# power.net
KiCad netlist of a schematic drawn in Altium Designer
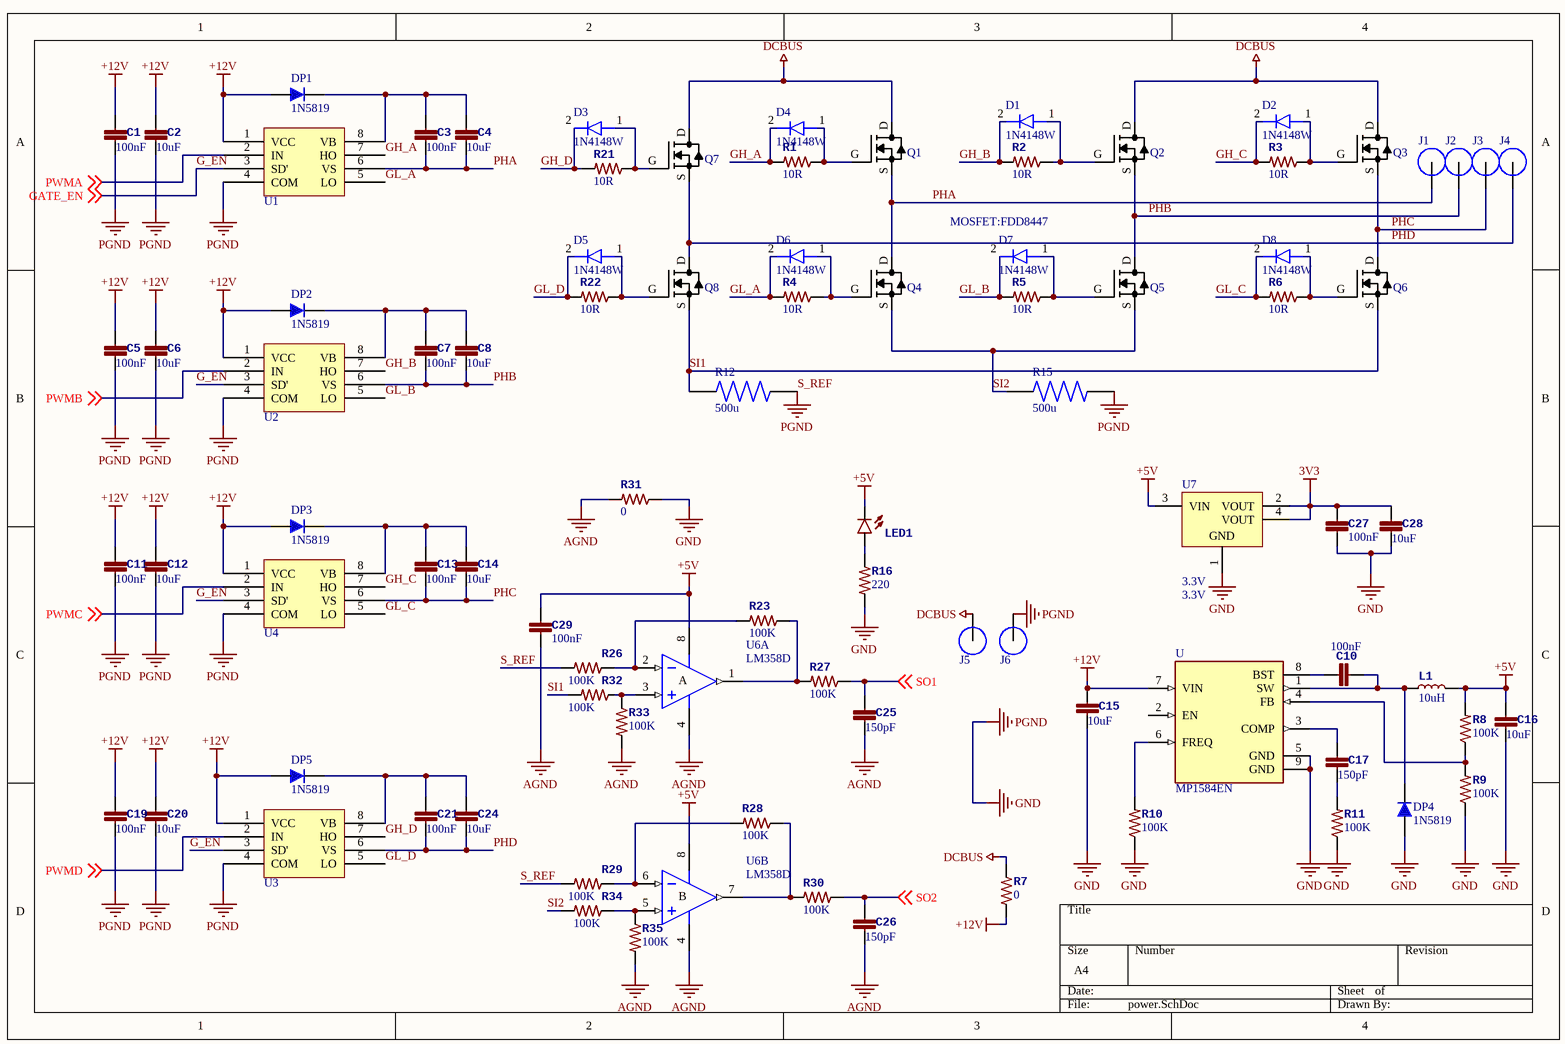
[diagram p0: power.SchDoc]

(export (version "E")
  (design (tool "Eeschema 10.0.6"))
  (components
    (comp (ref "C1")
      (value "100nF")
      (footprint "_1206")
      (fields (field (name "Comment") "Cap"))
      (libsource (lib "Passives_Integrated_Library") (part "Cap_1"))
    )
    (comp (ref "C2")
      (value "10uF")
      (footprint "_1206")
      (fields (field (name "Comment") "Cap"))
      (libsource (lib "Passives_Integrated_Library") (part "Cap_1"))
    )
    (comp (ref "C3")
      (value "100nF")
      (footprint "_1206")
      (fields (field (name "Comment") "Cap"))
      (libsource (lib "Passives_Integrated_Library") (part "Cap_1"))
    )
    (comp (ref "C4")
      (value "10uF")
      (footprint "_1206")
      (fields (field (name "Comment") "Cap"))
      (libsource (lib "Passives_Integrated_Library") (part "Cap_1"))
    )
    (comp (ref "C5")
      (value "100nF")
      (footprint "_1206")
      (fields (field (name "Comment") "Cap"))
      (libsource (lib "Passives_Integrated_Library") (part "Cap_1"))
    )
    (comp (ref "C6")
      (value "10uF")
      (footprint "_1206")
      (fields (field (name "Comment") "Cap"))
      (libsource (lib "Passives_Integrated_Library") (part "Cap_1"))
    )
    (comp (ref "C7")
      (value "100nF")
      (footprint "_1206")
      (fields (field (name "Comment") "Cap"))
      (libsource (lib "Passives_Integrated_Library") (part "Cap_1"))
    )
    (comp (ref "C8")
      (value "10uF")
      (footprint "_1206")
      (fields (field (name "Comment") "Cap"))
      (libsource (lib "Passives_Integrated_Library") (part "Cap_1"))
    )
    (comp (ref "C10")
      (value "100nF")
      (footprint "_0805")
      (fields (field (name "Comment") "Cap"))
      (libsource (lib "") (part "Cap_1_1"))
    )
    (comp (ref "C11")
      (value "100nF")
      (footprint "_1206")
      (fields (field (name "Comment") "Cap"))
      (libsource (lib "Passives_Integrated_Library") (part "Cap_1"))
    )
    (comp (ref "C12")
      (value "10uF")
      (footprint "_1206")
      (fields (field (name "Comment") "Cap"))
      (libsource (lib "Passives_Integrated_Library") (part "Cap_1"))
    )
    (comp (ref "C13")
      (value "100nF")
      (footprint "_1206")
      (fields (field (name "Comment") "Cap"))
      (libsource (lib "Passives_Integrated_Library") (part "Cap_1"))
    )
    (comp (ref "C14")
      (value "10uF")
      (footprint "_1206")
      (fields (field (name "Comment") "Cap"))
      (libsource (lib "Passives_Integrated_Library") (part "Cap_1"))
    )
    (comp (ref "C15")
      (value "10uF")
      (footprint "_1206")
      (fields (field (name "Comment") "Cap"))
      (libsource (lib "Passives_Integrated_Library") (part "Cap_1"))
    )
    (comp (ref "C16")
      (value "10uF")
      (footprint "_1206")
      (fields (field (name "Comment") "Cap"))
      (libsource (lib "Passives_Integrated_Library") (part "Cap_1"))
    )
    (comp (ref "C17")
      (value "150pF")
      (footprint "_0805")
      (fields (field (name "Comment") "Cap"))
      (libsource (lib "Passives_Integrated_Library") (part "Cap_1"))
    )
    (comp (ref "C19")
      (value "100nF")
      (footprint "_1206")
      (fields (field (name "Comment") "Cap"))
      (libsource (lib "Passives_Integrated_Library") (part "Cap_1"))
    )
    (comp (ref "C20")
      (value "10uF")
      (footprint "_1206")
      (fields (field (name "Comment") "Cap"))
      (libsource (lib "Passives_Integrated_Library") (part "Cap_1"))
    )
    (comp (ref "C21")
      (value "100nF")
      (footprint "_1206")
      (fields (field (name "Comment") "Cap"))
      (libsource (lib "Passives_Integrated_Library") (part "Cap_1"))
    )
    (comp (ref "C24")
      (value "10uF")
      (footprint "_1206")
      (fields (field (name "Comment") "Cap"))
      (libsource (lib "Passives_Integrated_Library") (part "Cap_1"))
    )
    (comp (ref "C25")
      (value "150pF")
      (footprint "_0805")
      (fields (field (name "Comment") "Cap"))
      (libsource (lib "Passives_Integrated_Library") (part "Cap_1"))
    )
    (comp (ref "C26")
      (value "150pF")
      (footprint "_0805")
      (fields (field (name "Comment") "Cap"))
      (libsource (lib "Passives_Integrated_Library") (part "Cap_1"))
    )
    (comp (ref "C27")
      (value "100nF")
      (footprint "_0805")
      (fields (field (name "Comment") "Cap"))
      (libsource (lib "") (part "Cap_1_2"))
    )
    (comp (ref "C28")
      (value "10uF")
      (footprint "_1206")
      (fields (field (name "Comment") "Cap"))
      (libsource (lib "Passives_Integrated_Library") (part "Cap_1"))
    )
    (comp (ref "C29")
      (value "100nF")
      (footprint "_0805")
      (fields (field (name "Comment") "Cap"))
      (libsource (lib "") (part "Cap_1_2"))
    )
    (comp (ref "D1")
      (value "1N4148W")
      (footprint "SOD523F")
      (fields (field (name "MF") "Micro Commercial"))
      (libsource (lib "1N4148W") (part "1N4148W"))
    )
    (comp (ref "D2")
      (value "1N4148W")
      (footprint "SOD523F")
      (fields (field (name "MF") "Micro Commercial"))
      (libsource (lib "1N4148W") (part "1N4148W"))
    )
    (comp (ref "D3")
      (value "1N4148W")
      (footprint "SOD523F")
      (fields (field (name "MF") "Micro Commercial"))
      (libsource (lib "1N4148W") (part "1N4148W"))
    )
    (comp (ref "D4")
      (value "1N4148W")
      (footprint "SOD523F")
      (fields (field (name "MF") "Micro Commercial"))
      (libsource (lib "1N4148W") (part "1N4148W"))
    )
    (comp (ref "D5")
      (value "1N4148W")
      (footprint "SOD523F")
      (fields (field (name "MF") "Micro Commercial"))
      (libsource (lib "1N4148W") (part "1N4148W"))
    )
    (comp (ref "D6")
      (value "1N4148W")
      (footprint "SOD523F")
      (fields (field (name "MF") "Micro Commercial"))
      (libsource (lib "1N4148W") (part "1N4148W"))
    )
    (comp (ref "D7")
      (value "1N4148W")
      (footprint "SOD523F")
      (fields (field (name "MF") "Micro Commercial"))
      (libsource (lib "1N4148W") (part "1N4148W"))
    )
    (comp (ref "D8")
      (value "1N4148W")
      (footprint "SOD523F")
      (fields (field (name "MF") "Micro Commercial"))
      (libsource (lib "1N4148W") (part "1N4148W"))
    )
    (comp (ref "DP1")
      (value "1N5819")
      (footprint "430X270D")
      (description "Schottkey Rectifiers")
      (fields (field (name "DESIGNER") "Abbas Basereh"))
      (libsource (lib "Diodes_Integrated_Library") (part "1N5819"))
    )
    (comp (ref "DP2")
      (value "1N5819")
      (footprint "430X270D")
      (description "Schottkey Rectifiers")
      (fields (field (name "DESIGNER") "Abbas Basereh"))
      (libsource (lib "Diodes_Integrated_Library") (part "1N5819"))
    )
    (comp (ref "DP3")
      (value "1N5819")
      (footprint "430X270D")
      (description "Schottkey Rectifiers")
      (fields (field (name "DESIGNER") "Abbas Basereh"))
      (libsource (lib "Diodes_Integrated_Library") (part "1N5819"))
    )
    (comp (ref "DP4")
      (value "1N5819")
      (footprint "430X270D")
      (description "Schottkey Rectifiers")
      (fields (field (name "DESIGNER") "Abbas Basereh"))
      (libsource (lib "Diodes_Integrated_Library") (part "1N5819"))
    )
    (comp (ref "DP5")
      (value "1N5819")
      (footprint "430X270D")
      (description "Schottkey Rectifiers")
      (fields (field (name "DESIGNER") "Abbas Basereh"))
      (libsource (lib "Diodes_Integrated_Library") (part "1N5819"))
    )
    (comp (ref "J1")
      (value "~")
      (footprint "M3 Spade Hole")
      (description "M3 Spade Terminal")
      (libsource (lib "CustomComponents") (part "M3 Spade Terminal"))
    )
    (comp (ref "J2")
      (value "~")
      (footprint "M3 Spade Hole")
      (description "M3 Spade Terminal")
      (libsource (lib "CustomComponents") (part "M3 Spade Terminal"))
    )
    (comp (ref "J3")
      (value "~")
      (footprint "M3 Spade Hole")
      (description "M3 Spade Terminal")
      (libsource (lib "CustomComponents") (part "M3 Spade Terminal"))
    )
    (comp (ref "J4")
      (value "~")
      (footprint "M3 Spade Hole")
      (description "M3 Spade Terminal")
      (libsource (lib "ali_drv_parts") (part "M3 Spade Terminal"))
    )
    (comp (ref "J5")
      (value "~")
      (footprint "M3 Spade Hole")
      (description "M3 Spade Terminal")
      (libsource (lib "CustomComponents") (part "M3 Spade Terminal"))
    )
    (comp (ref "J6")
      (value "~")
      (footprint "M3 Spade Hole")
      (description "M3 Spade Terminal")
      (libsource (lib "CustomComponents") (part "M3 Spade Terminal"))
    )
    (comp (ref "L1")
      (value "10uH")
      (footprint "_INDUCTOR-SMD-6.0mm")
      (fields (field (name "Comment") "Inductor"))
      (libsource (lib "Passives_Integrated_Library") (part "Inductor"))
    )
    (comp (ref "LED1")
      (value "LED")
      (footprint "_LED-0805")
      (libsource (lib "Diodes_Integrated_Library") (part "LED"))
    )
    (comp (ref "Q1")
      (value "FILL_FOOTPRINT")
      (footprint "TO229P994X240-3N")
      (description "MOSFET N-CH 30V 13A SO8FL")
      (fields
        (field (name "MANUFACTURER") "ON Semiconductor")
        (field (name "MANUFACTURER PART NUMBER") "NTMFS4935NT1G")
      )
      (libsource (lib "Integrated_Library1") (part "NTMFS4935NT1G"))
    )
    (comp (ref "Q2")
      (value "FILL_FOOTPRINT")
      (footprint "TO229P994X240-3N")
      (description "MOSFET N-CH 30V 13A SO8FL")
      (fields
        (field (name "MANUFACTURER") "ON Semiconductor")
        (field (name "MANUFACTURER PART NUMBER") "NTMFS4935NT1G")
      )
      (libsource (lib "Integrated_Library1") (part "NTMFS4935NT1G"))
    )
    (comp (ref "Q3")
      (value "FILL_FOOTPRINT")
      (footprint "TO229P994X240-3N")
      (description "MOSFET N-CH 30V 13A SO8FL")
      (fields
        (field (name "MANUFACTURER") "ON Semiconductor")
        (field (name "MANUFACTURER PART NUMBER") "NTMFS4935NT1G")
      )
      (libsource (lib "Integrated_Library1") (part "NTMFS4935NT1G"))
    )
    (comp (ref "Q4")
      (value "FILL_FOOTPRINT")
      (footprint "TO229P994X240-3N")
      (description "MOSFET N-CH 30V 13A SO8FL")
      (fields
        (field (name "MANUFACTURER") "ON Semiconductor")
        (field (name "MANUFACTURER PART NUMBER") "NTMFS4935NT1G")
      )
      (libsource (lib "Integrated_Library1") (part "NTMFS4935NT1G"))
    )
    (comp (ref "Q5")
      (value "FILL_FOOTPRINT")
      (footprint "TO229P994X240-3N")
      (description "MOSFET N-CH 30V 13A SO8FL")
      (fields
        (field (name "MANUFACTURER") "ON Semiconductor")
        (field (name "MANUFACTURER PART NUMBER") "NTMFS4935NT1G")
      )
      (libsource (lib "Integrated_Library1") (part "NTMFS4935NT1G"))
    )
    (comp (ref "Q6")
      (value "FILL_FOOTPRINT")
      (footprint "TO229P994X240-3N")
      (description "MOSFET N-CH 30V 13A SO8FL")
      (fields
        (field (name "MANUFACTURER") "ON Semiconductor")
        (field (name "MANUFACTURER PART NUMBER") "NTMFS4935NT1G")
      )
      (libsource (lib "Integrated_Library1") (part "NTMFS4935NT1G"))
    )
    (comp (ref "Q7")
      (value "FILL_FOOTPRINT")
      (footprint "TO229P994X240-3N")
      (description "MOSFET N-CH 30V 13A SO8FL")
      (fields
        (field (name "MANUFACTURER") "ON Semiconductor")
        (field (name "MANUFACTURER PART NUMBER") "NTMFS4935NT1G")
      )
      (libsource (lib "ali_drv_parts") (part "NTMFS4935NT1G"))
    )
    (comp (ref "Q8")
      (value "FILL_FOOTPRINT")
      (footprint "TO229P994X240-3N")
      (description "MOSFET N-CH 30V 13A SO8FL")
      (fields
        (field (name "MANUFACTURER") "ON Semiconductor")
        (field (name "MANUFACTURER PART NUMBER") "NTMFS4935NT1G")
      )
      (libsource (lib "ali_drv_parts") (part "NTMFS4935NT1G"))
    )
    (comp (ref "R1")
      (value "10R")
      (footprint "_0805")
      (fields (field (name "Comment") "Resistor"))
      (libsource (lib "Passives_Integrated_Library") (part "Resistor"))
    )
    (comp (ref "R2")
      (value "10R")
      (footprint "_0805")
      (fields (field (name "Comment") "Resistor"))
      (libsource (lib "Passives_Integrated_Library") (part "Resistor"))
    )
    (comp (ref "R3")
      (value "10R")
      (footprint "_0805")
      (fields (field (name "Comment") "Resistor"))
      (libsource (lib "Passives_Integrated_Library") (part "Resistor"))
    )
    (comp (ref "R4")
      (value "10R")
      (footprint "_0805")
      (fields (field (name "Comment") "Resistor"))
      (libsource (lib "Passives_Integrated_Library") (part "Resistor"))
    )
    (comp (ref "R5")
      (value "10R")
      (footprint "_0805")
      (fields (field (name "Comment") "Resistor"))
      (libsource (lib "Passives_Integrated_Library") (part "Resistor"))
    )
    (comp (ref "R6")
      (value "10R")
      (footprint "_0805")
      (fields (field (name "Comment") "Resistor"))
      (libsource (lib "Passives_Integrated_Library") (part "Resistor"))
    )
    (comp (ref "R7")
      (value "0")
      (footprint "_1206")
      (fields (field (name "Comment") "Resistor"))
      (libsource (lib "Passives_Integrated_Library") (part "Resistor"))
    )
    (comp (ref "R8")
      (value "100K")
      (footprint "_0805")
      (fields (field (name "Comment") "Resistor"))
      (libsource (lib "Passives_Integrated_Library") (part "Resistor"))
    )
    (comp (ref "R9")
      (value "100K")
      (footprint "_0805")
      (fields (field (name "Comment") "Resistor"))
      (libsource (lib "Passives_Integrated_Library") (part "Resistor"))
    )
    (comp (ref "R10")
      (value "100K")
      (footprint "_0805")
      (fields (field (name "Comment") "Resistor"))
      (libsource (lib "Passives_Integrated_Library") (part "Resistor"))
    )
    (comp (ref "R11")
      (value "100K")
      (footprint "_0805")
      (fields (field (name "Comment") "Resistor"))
      (libsource (lib "Passives_Integrated_Library") (part "Resistor"))
    )
    (comp (ref "R12")
      (value "500u")
      (footprint "RESC6332X64N")
      (fields (field (name "MP") "Y162820K0000D0W"))
      (libsource (lib "ali_drv_parts") (part "Y162820K0000D0W"))
    )
    (comp (ref "R15")
      (value "500u")
      (footprint "RESC6332X64N")
      (fields (field (name "MP") "Y162820K0000D0W"))
      (libsource (lib "ali_drv_parts") (part "Y162820K0000D0W"))
    )
    (comp (ref "R16")
      (value "220")
      (footprint "_0805")
      (fields (field (name "Comment") "Resistor"))
      (libsource (lib "Passives_Integrated_Library") (part "Resistor"))
    )
    (comp (ref "R21")
      (value "10R")
      (footprint "_0805")
      (fields (field (name "Comment") "Resistor"))
      (libsource (lib "Passives_Integrated_Library") (part "Resistor"))
    )
    (comp (ref "R22")
      (value "10R")
      (footprint "_0805")
      (fields (field (name "Comment") "Resistor"))
      (libsource (lib "Passives_Integrated_Library") (part "Resistor"))
    )
    (comp (ref "R23")
      (value "100K")
      (footprint "_0805")
      (fields (field (name "Comment") "Resistor"))
      (libsource (lib "Passives_Integrated_Library") (part "Resistor"))
    )
    (comp (ref "R26")
      (value "100K")
      (footprint "_0805")
      (fields (field (name "Comment") "Resistor"))
      (libsource (lib "Passives_Integrated_Library") (part "Resistor"))
    )
    (comp (ref "R27")
      (value "100K")
      (footprint "_0805")
      (fields (field (name "Comment") "Resistor"))
      (libsource (lib "Passives_Integrated_Library") (part "Resistor"))
    )
    (comp (ref "R28")
      (value "100K")
      (footprint "_0805")
      (fields (field (name "Comment") "Resistor"))
      (libsource (lib "Passives_Integrated_Library") (part "Resistor"))
    )
    (comp (ref "R29")
      (value "100K")
      (footprint "_0805")
      (fields (field (name "Comment") "Resistor"))
      (libsource (lib "Passives_Integrated_Library") (part "Resistor"))
    )
    (comp (ref "R30")
      (value "100K")
      (footprint "_0805")
      (fields (field (name "Comment") "Resistor"))
      (libsource (lib "Passives_Integrated_Library") (part "Resistor"))
    )
    (comp (ref "R31")
      (value "0")
      (footprint "_0805")
      (fields (field (name "Comment") "Resistor"))
      (libsource (lib "Passives_Integrated_Library") (part "Resistor"))
    )
    (comp (ref "R32")
      (value "100K")
      (footprint "_0805")
      (fields (field (name "Comment") "Resistor"))
      (libsource (lib "Passives_Integrated_Library") (part "Resistor"))
    )
    (comp (ref "R33")
      (value "100K")
      (footprint "_0805")
      (fields (field (name "Comment") "Resistor"))
      (libsource (lib "Passives_Integrated_Library") (part "Resistor"))
    )
    (comp (ref "R34")
      (value "100K")
      (footprint "_0805")
      (fields (field (name "Comment") "Resistor"))
      (libsource (lib "Passives_Integrated_Library") (part "Resistor"))
    )
    (comp (ref "R35")
      (value "100K")
      (footprint "_0805")
      (fields (field (name "Comment") "Resistor"))
      (libsource (lib "Passives_Integrated_Library") (part "Resistor"))
    )
    (comp (ref "U")
      (value "MP1584EN")
      (footprint "SOIC127P600X170-9N")
      (fields (field (name "MF") "Monolithic Power"))
      (libsource (lib "MP1584EN") (part "MP1584EN"))
    )
    (comp (ref "U1")
      (value "IR2104")
      (footprint "_SO08")
      (libsource (lib "Power_Electronics_Integrated_Library") (part "IR2104"))
    )
    (comp (ref "U2")
      (value "IR2104")
      (footprint "_SO08")
      (libsource (lib "Power_Electronics_Integrated_Library") (part "IR2104"))
    )
    (comp (ref "U3")
      (value "IR2104")
      (footprint "_SO08")
      (libsource (lib "Power_Electronics_Integrated_Library") (part "IR2104"))
    )
    (comp (ref "U4")
      (value "IR2104")
      (footprint "_SO08")
      (libsource (lib "Power_Electronics_Integrated_Library") (part "IR2104"))
    )
    (comp (ref "U6")
      (value "LM358D")
      (footprint "D008_L")
      (description "Dual Operational Amplifier")
      (fields (field (name "PUBLISHER") "Altium Limited"))
      (libsource (lib "TI Operational Amplifier") (part "LM358D"))
    )
    (comp (ref "U7")
      (value "3.3V")
      (footprint "_SOT223")
      (fields (field (name "ALTIUM_VALUE") "3.3V"))
      (libsource (lib "Regulators_Integrated_Library") (part "LD1117"))
    )
  )
  (nets
    (net (code "1") (name "+5V") (class "Default")
      (node (ref "C16") (pin "1") (pinfunction "1_1") (pintype "passive"))
      (node (ref "C29") (pin "2") (pinfunction "2_2") (pintype "passive"))
      (node (ref "L1") (pin "2") (pinfunction "2_2") (pintype "passive"))
      (node (ref "LED1") (pin "K") (pinfunction "K_K") (pintype "passive"))
      (node (ref "R8") (pin "2") (pinfunction "2_2") (pintype "passive"))
      (node (ref "U6") (pin "8") (pinfunction "V+_8") (pintype "power_in"))
      (node (ref "U7") (pin "3") (pinfunction "VIN_3") (pintype "power_in"))
    )
    (net (code "2") (name "+12V") (class "Default")
      (node (ref "C1") (pin "1") (pinfunction "1_1") (pintype "passive"))
      (node (ref "C11") (pin "1") (pinfunction "1_1") (pintype "passive"))
      (node (ref "C12") (pin "1") (pinfunction "1_1") (pintype "passive"))
      (node (ref "C15") (pin "1") (pinfunction "1_1") (pintype "passive"))
      (node (ref "C19") (pin "1") (pinfunction "1_1") (pintype "passive"))
      (node (ref "C2") (pin "1") (pinfunction "1_1") (pintype "passive"))
      (node (ref "C20") (pin "1") (pinfunction "1_1") (pintype "passive"))
      (node (ref "C5") (pin "1") (pinfunction "1_1") (pintype "passive"))
      (node (ref "C6") (pin "1") (pinfunction "1_1") (pintype "passive"))
      (node (ref "DP1") (pin "1") (pintype "passive"))
      (node (ref "DP2") (pin "1") (pintype "passive"))
      (node (ref "DP3") (pin "1") (pintype "passive"))
      (node (ref "DP5") (pin "1") (pintype "passive"))
      (node (ref "R7") (pin "2") (pinfunction "2_2") (pintype "passive"))
      (node (ref "U") (pin "7") (pinfunction "VIN_7") (pintype "input"))
      (node (ref "U1") (pin "1") (pinfunction "VCC_1") (pintype "passive"))
      (node (ref "U2") (pin "1") (pinfunction "VCC_1") (pintype "passive"))
      (node (ref "U3") (pin "1") (pinfunction "VCC_1") (pintype "passive"))
      (node (ref "U4") (pin "1") (pinfunction "VCC_1") (pintype "passive"))
    )
    (net (code "3") (name "/GH_A") (class "Default")
      (node (ref "D4") (pin "2") (pinfunction "C1_2") (pintype "passive"))
      (node (ref "R1") (pin "2") (pinfunction "2_2") (pintype "passive"))
      (node (ref "U1") (pin "7") (pinfunction "HO_7") (pintype "passive"))
    )
    (net (code "4") (name "/GH_B") (class "Default")
      (node (ref "D1") (pin "2") (pinfunction "C1_2") (pintype "passive"))
      (node (ref "R2") (pin "2") (pinfunction "2_2") (pintype "passive"))
      (node (ref "U2") (pin "7") (pinfunction "HO_7") (pintype "passive"))
    )
    (net (code "5") (name "/GH_C") (class "Default")
      (node (ref "D2") (pin "2") (pinfunction "C1_2") (pintype "passive"))
      (node (ref "R3") (pin "2") (pinfunction "2_2") (pintype "passive"))
      (node (ref "U4") (pin "7") (pinfunction "HO_7") (pintype "passive"))
    )
    (net (code "6") (name "/GH_D") (class "Default")
      (node (ref "D3") (pin "2") (pinfunction "C1_2") (pintype "passive"))
      (node (ref "R21") (pin "2") (pinfunction "2_2") (pintype "passive"))
      (node (ref "U3") (pin "7") (pinfunction "HO_7") (pintype "passive"))
    )
    (net (code "7") (name "/GL_A") (class "Default")
      (node (ref "D6") (pin "2") (pinfunction "C1_2") (pintype "passive"))
      (node (ref "R4") (pin "2") (pinfunction "2_2") (pintype "passive"))
      (node (ref "U1") (pin "5") (pinfunction "LO_5") (pintype "passive"))
    )
    (net (code "8") (name "/GL_B") (class "Default")
      (node (ref "D7") (pin "2") (pinfunction "C1_2") (pintype "passive"))
      (node (ref "R5") (pin "2") (pinfunction "2_2") (pintype "passive"))
      (node (ref "U2") (pin "5") (pinfunction "LO_5") (pintype "passive"))
    )
    (net (code "9") (name "/GL_C") (class "Default")
      (node (ref "D8") (pin "2") (pinfunction "C1_2") (pintype "passive"))
      (node (ref "R6") (pin "2") (pinfunction "2_2") (pintype "passive"))
      (node (ref "U4") (pin "5") (pinfunction "LO_5") (pintype "passive"))
    )
    (net (code "10") (name "/GL_D") (class "Default")
      (node (ref "D5") (pin "2") (pinfunction "C1_2") (pintype "passive"))
      (node (ref "R22") (pin "2") (pinfunction "2_2") (pintype "passive"))
      (node (ref "U3") (pin "5") (pinfunction "LO_5") (pintype "passive"))
    )
    (net (code "11") (name "/PHA") (class "Default")
      (node (ref "C3") (pin "2") (pinfunction "2_2") (pintype "passive"))
      (node (ref "C4") (pin "2") (pinfunction "2_2") (pintype "passive"))
      (node (ref "J1") (pin "1") (pinfunction "1_1") (pintype "passive"))
      (node (ref "Q1") (pin "S") (pinfunction "S_S") (pintype "passive"))
      (node (ref "Q4") (pin "D") (pinfunction "D_D") (pintype "passive"))
      (node (ref "U1") (pin "6") (pinfunction "VS_6") (pintype "passive"))
    )
    (net (code "12") (name "/PHB") (class "Default")
      (node (ref "C7") (pin "2") (pinfunction "2_2") (pintype "passive"))
      (node (ref "C8") (pin "2") (pinfunction "2_2") (pintype "passive"))
      (node (ref "J2") (pin "1") (pinfunction "1_1") (pintype "passive"))
      (node (ref "Q2") (pin "S") (pinfunction "S_S") (pintype "passive"))
      (node (ref "Q5") (pin "D") (pinfunction "D_D") (pintype "passive"))
      (node (ref "U2") (pin "6") (pinfunction "VS_6") (pintype "passive"))
    )
    (net (code "13") (name "/PHC") (class "Default")
      (node (ref "C13") (pin "2") (pinfunction "2_2") (pintype "passive"))
      (node (ref "C14") (pin "2") (pinfunction "2_2") (pintype "passive"))
      (node (ref "J3") (pin "1") (pinfunction "1_1") (pintype "passive"))
      (node (ref "Q3") (pin "S") (pinfunction "S_S") (pintype "passive"))
      (node (ref "Q6") (pin "D") (pinfunction "D_D") (pintype "passive"))
      (node (ref "U4") (pin "6") (pinfunction "VS_6") (pintype "passive"))
    )
    (net (code "14") (name "/PHD") (class "Default")
      (node (ref "C21") (pin "2") (pinfunction "2_2") (pintype "passive"))
      (node (ref "C24") (pin "2") (pinfunction "2_2") (pintype "passive"))
      (node (ref "J4") (pin "1") (pinfunction "1_1") (pintype "passive"))
      (node (ref "Q7") (pin "S") (pinfunction "S_S") (pintype "passive"))
      (node (ref "Q8") (pin "D") (pinfunction "D_D") (pintype "passive"))
      (node (ref "U3") (pin "6") (pinfunction "VS_6") (pintype "passive"))
    )
    (net (code "15") (name "/SI1") (class "Default")
      (node (ref "Q6") (pin "S") (pinfunction "S_S") (pintype "passive"))
      (node (ref "Q8") (pin "S") (pinfunction "S_S") (pintype "passive"))
      (node (ref "R12") (pin "2") (pinfunction "2_2") (pintype "passive"))
      (node (ref "R32") (pin "2") (pinfunction "2_2") (pintype "passive"))
    )
    (net (code "16") (name "/SI2") (class "Default")
      (node (ref "Q4") (pin "S") (pinfunction "S_S") (pintype "passive"))
      (node (ref "Q5") (pin "S") (pinfunction "S_S") (pintype "passive"))
      (node (ref "R15") (pin "2") (pinfunction "2_2") (pintype "passive"))
      (node (ref "R34") (pin "2") (pinfunction "2_2") (pintype "passive"))
    )
    (net (code "17") (name "3V3") (class "Default")
      (node (ref "C27") (pin "2") (pinfunction "2_2") (pintype "passive"))
      (node (ref "C28") (pin "1") (pinfunction "1_1") (pintype "passive"))
      (node (ref "U7") (pin "2") (pinfunction "VOUT_2") (pintype "power_in"))
      (node (ref "U7") (pin "4") (pinfunction "VOUT_4") (pintype "power_in"))
    )
    (net (code "18") (name "AGND") (class "Default")
      (node (ref "C25") (pin "2") (pinfunction "2_2") (pintype "passive"))
      (node (ref "C26") (pin "2") (pinfunction "2_2") (pintype "passive"))
      (node (ref "C29") (pin "1") (pinfunction "1_1") (pintype "passive"))
      (node (ref "R31") (pin "2") (pinfunction "2_2") (pintype "passive"))
      (node (ref "R33") (pin "2") (pinfunction "2_2") (pintype "passive"))
      (node (ref "R35") (pin "2") (pinfunction "2_2") (pintype "passive"))
      (node (ref "U6") (pin "4") (pinfunction "V-_4") (pintype "power_in"))
    )
    (net (code "19") (name "DCBUS") (class "Default")
      (node (ref "J5") (pin "1") (pinfunction "1_1") (pintype "passive"))
      (node (ref "Q1") (pin "D") (pinfunction "D_D") (pintype "passive"))
      (node (ref "Q2") (pin "D") (pinfunction "D_D") (pintype "passive"))
      (node (ref "Q3") (pin "D") (pinfunction "D_D") (pintype "passive"))
      (node (ref "Q7") (pin "D") (pinfunction "D_D") (pintype "passive"))
      (node (ref "R7") (pin "1") (pinfunction "1_1") (pintype "passive"))
    )
    (net (code "20") (name "GATE_EN") (class "Default")
      (node (ref "U1") (pin "3") (pinfunction "SD'_3") (pintype "passive"))
      (node (ref "U2") (pin "3") (pinfunction "SD'_3") (pintype "passive"))
      (node (ref "U3") (pin "3") (pinfunction "SD'_3") (pintype "passive"))
      (node (ref "U4") (pin "3") (pinfunction "SD'_3") (pintype "passive"))
    )
    (net (code "21") (name "GND") (class "Default")
      (node (ref "C1") (pin "2") (pinfunction "2_2") (pintype "passive"))
      (node (ref "C11") (pin "2") (pinfunction "2_2") (pintype "passive"))
      (node (ref "C12") (pin "2") (pinfunction "2_2") (pintype "passive"))
      (node (ref "C15") (pin "2") (pinfunction "2_2") (pintype "passive"))
      (node (ref "C16") (pin "2") (pinfunction "2_2") (pintype "passive"))
      (node (ref "C19") (pin "2") (pinfunction "2_2") (pintype "passive"))
      (node (ref "C2") (pin "2") (pinfunction "2_2") (pintype "passive"))
      (node (ref "C20") (pin "2") (pinfunction "2_2") (pintype "passive"))
      (node (ref "C27") (pin "1") (pinfunction "1_1") (pintype "passive"))
      (node (ref "C28") (pin "2") (pinfunction "2_2") (pintype "passive"))
      (node (ref "C5") (pin "2") (pinfunction "2_2") (pintype "passive"))
      (node (ref "C6") (pin "2") (pinfunction "2_2") (pintype "passive"))
      (node (ref "DP4") (pin "1") (pintype "passive"))
      (node (ref "J6") (pin "1") (pinfunction "1_1") (pintype "passive"))
      (node (ref "R10") (pin "1") (pinfunction "1_1") (pintype "passive"))
      (node (ref "R11") (pin "1") (pinfunction "1_1") (pintype "passive"))
      (node (ref "R12") (pin "1") (pinfunction "1_1") (pintype "passive"))
      (node (ref "R15") (pin "1") (pinfunction "1_1") (pintype "passive"))
      (node (ref "R16") (pin "2") (pinfunction "2_2") (pintype "passive"))
      (node (ref "R26") (pin "2") (pinfunction "2_2") (pintype "passive"))
      (node (ref "R29") (pin "2") (pinfunction "2_2") (pintype "passive"))
      (node (ref "R31") (pin "1") (pinfunction "1_1") (pintype "passive"))
      (node (ref "R9") (pin "1") (pinfunction "1_1") (pintype "passive"))
      (node (ref "U") (pin "5") (pinfunction "GND_5") (pintype "power_in"))
      (node (ref "U") (pin "9") (pinfunction "GND_9") (pintype "power_in"))
      (node (ref "U1") (pin "4") (pinfunction "COM_4") (pintype "passive"))
      (node (ref "U2") (pin "4") (pinfunction "COM_4") (pintype "passive"))
      (node (ref "U3") (pin "4") (pinfunction "COM_4") (pintype "passive"))
      (node (ref "U4") (pin "4") (pinfunction "COM_4") (pintype "passive"))
      (node (ref "U7") (pin "1") (pinfunction "GND_1") (pintype "power_in"))
    )
    (net (code "22") (name "Net-(C17-Pad2)") (class "Default")
      (node (ref "C17") (pin "2") (pinfunction "2_2") (pintype "passive"))
      (node (ref "R11") (pin "2") (pinfunction "2_2") (pintype "passive"))
    )
    (net (code "23") (name "Net-(D1-A1)") (class "Default")
      (node (ref "D1") (pin "1") (pinfunction "A1_1") (pintype "passive"))
      (node (ref "Q2") (pin "G") (pinfunction "G_G") (pintype "passive"))
      (node (ref "R2") (pin "1") (pinfunction "1_1") (pintype "passive"))
    )
    (net (code "24") (name "Net-(D2-A1)") (class "Default")
      (node (ref "D2") (pin "1") (pinfunction "A1_1") (pintype "passive"))
      (node (ref "Q3") (pin "G") (pinfunction "G_G") (pintype "passive"))
      (node (ref "R3") (pin "1") (pinfunction "1_1") (pintype "passive"))
    )
    (net (code "25") (name "Net-(D3-A1)") (class "Default")
      (node (ref "D3") (pin "1") (pinfunction "A1_1") (pintype "passive"))
      (node (ref "Q7") (pin "G") (pinfunction "G_G") (pintype "passive"))
      (node (ref "R21") (pin "1") (pinfunction "1_1") (pintype "passive"))
    )
    (net (code "26") (name "Net-(D4-A1)") (class "Default")
      (node (ref "D4") (pin "1") (pinfunction "A1_1") (pintype "passive"))
      (node (ref "Q1") (pin "G") (pinfunction "G_G") (pintype "passive"))
      (node (ref "R1") (pin "1") (pinfunction "1_1") (pintype "passive"))
    )
    (net (code "27") (name "Net-(D5-A1)") (class "Default")
      (node (ref "D5") (pin "1") (pinfunction "A1_1") (pintype "passive"))
      (node (ref "Q8") (pin "G") (pinfunction "G_G") (pintype "passive"))
      (node (ref "R22") (pin "1") (pinfunction "1_1") (pintype "passive"))
    )
    (net (code "28") (name "Net-(D6-A1)") (class "Default")
      (node (ref "D6") (pin "1") (pinfunction "A1_1") (pintype "passive"))
      (node (ref "Q4") (pin "G") (pinfunction "G_G") (pintype "passive"))
      (node (ref "R4") (pin "1") (pinfunction "1_1") (pintype "passive"))
    )
    (net (code "29") (name "Net-(D7-A1)") (class "Default")
      (node (ref "D7") (pin "1") (pinfunction "A1_1") (pintype "passive"))
      (node (ref "Q5") (pin "G") (pinfunction "G_G") (pintype "passive"))
      (node (ref "R5") (pin "1") (pinfunction "1_1") (pintype "passive"))
    )
    (net (code "30") (name "Net-(D8-A1)") (class "Default")
      (node (ref "D8") (pin "1") (pinfunction "A1_1") (pintype "passive"))
      (node (ref "Q6") (pin "G") (pinfunction "G_G") (pintype "passive"))
      (node (ref "R6") (pin "1") (pinfunction "1_1") (pintype "passive"))
    )
    (net (code "31") (name "Net-(LED1-PadA)") (class "Default")
      (node (ref "LED1") (pin "A") (pinfunction "A_A") (pintype "passive"))
      (node (ref "R16") (pin "1") (pinfunction "1_1") (pintype "passive"))
    )
    (net (code "32") (name "Net-(U-BST)") (class "Default")
      (node (ref "C10") (pin "1") (pinfunction "1_1") (pintype "passive"))
      (node (ref "U") (pin "8") (pinfunction "BST_8") (pintype "passive"))
    )
    (net (code "33") (name "Net-(U-COMP)") (class "Default")
      (node (ref "C17") (pin "1") (pinfunction "1_1") (pintype "passive"))
      (node (ref "U") (pin "3") (pinfunction "COMP_3") (pintype "output"))
    )
    (net (code "34") (name "Net-(U-FB)") (class "Default")
      (node (ref "R8") (pin "1") (pinfunction "1_1") (pintype "passive"))
      (node (ref "R9") (pin "2") (pinfunction "2_2") (pintype "passive"))
      (node (ref "U") (pin "4") (pinfunction "FB_4") (pintype "input"))
    )
    (net (code "35") (name "Net-(U-FREQ)") (class "Default")
      (node (ref "R10") (pin "2") (pinfunction "2_2") (pintype "passive"))
      (node (ref "U") (pin "6") (pinfunction "FREQ_6") (pintype "input"))
    )
    (net (code "36") (name "Net-(U-SW)") (class "Default")
      (node (ref "C10") (pin "2") (pinfunction "2_2") (pintype "passive"))
      (node (ref "DP4") (pin "2") (pintype "passive"))
      (node (ref "L1") (pin "1") (pinfunction "1_1") (pintype "passive"))
      (node (ref "U") (pin "1") (pinfunction "SW_1") (pintype "output"))
    )
    (net (code "37") (name "Net-(U1-VB)") (class "Default")
      (node (ref "C3") (pin "1") (pinfunction "1_1") (pintype "passive"))
      (node (ref "C4") (pin "1") (pinfunction "1_1") (pintype "passive"))
      (node (ref "DP1") (pin "2") (pintype "passive"))
      (node (ref "U1") (pin "8") (pinfunction "VB_8") (pintype "passive"))
    )
    (net (code "38") (name "Net-(U2-VB)") (class "Default")
      (node (ref "C7") (pin "1") (pinfunction "1_1") (pintype "passive"))
      (node (ref "C8") (pin "1") (pinfunction "1_1") (pintype "passive"))
      (node (ref "DP2") (pin "2") (pintype "passive"))
      (node (ref "U2") (pin "8") (pinfunction "VB_8") (pintype "passive"))
    )
    (net (code "39") (name "Net-(U3-VB)") (class "Default")
      (node (ref "C21") (pin "1") (pinfunction "1_1") (pintype "passive"))
      (node (ref "C24") (pin "1") (pinfunction "1_1") (pintype "passive"))
      (node (ref "DP5") (pin "2") (pintype "passive"))
      (node (ref "U3") (pin "8") (pinfunction "VB_8") (pintype "passive"))
    )
    (net (code "40") (name "Net-(U4-VB)") (class "Default")
      (node (ref "C13") (pin "1") (pinfunction "1_1") (pintype "passive"))
      (node (ref "C14") (pin "1") (pinfunction "1_1") (pintype "passive"))
      (node (ref "DP3") (pin "2") (pintype "passive"))
      (node (ref "U4") (pin "8") (pinfunction "VB_8") (pintype "passive"))
    )
    (net (code "41") (name "Net-(U6A-IN+)") (class "Default")
      (node (ref "R32") (pin "1") (pinfunction "1_1") (pintype "passive"))
      (node (ref "R33") (pin "1") (pinfunction "1_1") (pintype "passive"))
      (node (ref "U6") (pin "3") (pinfunction "IN+_3") (pintype "input"))
    )
    (net (code "42") (name "Net-(U6A-IN-)") (class "Default")
      (node (ref "R23") (pin "2") (pinfunction "2_2") (pintype "passive"))
      (node (ref "R26") (pin "1") (pinfunction "1_1") (pintype "passive"))
      (node (ref "U6") (pin "2") (pinfunction "IN-_2") (pintype "input"))
    )
    (net (code "43") (name "Net-(U6A-OUT)") (class "Default")
      (node (ref "R23") (pin "1") (pinfunction "1_1") (pintype "passive"))
      (node (ref "R27") (pin "2") (pinfunction "2_2") (pintype "passive"))
      (node (ref "U6") (pin "1") (pinfunction "OUT_1") (pintype "output"))
    )
    (net (code "44") (name "Net-(U6B-IN+)") (class "Default")
      (node (ref "R34") (pin "1") (pinfunction "1_1") (pintype "passive"))
      (node (ref "R35") (pin "1") (pinfunction "1_1") (pintype "passive"))
      (node (ref "U6") (pin "5") (pinfunction "IN+_5") (pintype "input"))
    )
    (net (code "45") (name "Net-(U6B-IN-)") (class "Default")
      (node (ref "R28") (pin "2") (pinfunction "2_2") (pintype "passive"))
      (node (ref "R29") (pin "1") (pinfunction "1_1") (pintype "passive"))
      (node (ref "U6") (pin "6") (pinfunction "IN-_6") (pintype "input"))
    )
    (net (code "46") (name "Net-(U6B-OUT)") (class "Default")
      (node (ref "R28") (pin "1") (pinfunction "1_1") (pintype "passive"))
      (node (ref "R30") (pin "2") (pinfunction "2_2") (pintype "passive"))
      (node (ref "U6") (pin "7") (pinfunction "OUT_7") (pintype "output"))
    )
    (net (code "47") (name "PWMA") (class "Default")
      (node (ref "U1") (pin "2") (pinfunction "IN_2") (pintype "passive"))
    )
    (net (code "48") (name "PWMB") (class "Default")
      (node (ref "U2") (pin "2") (pinfunction "IN_2") (pintype "passive"))
    )
    (net (code "49") (name "PWMC") (class "Default")
      (node (ref "U4") (pin "2") (pinfunction "IN_2") (pintype "passive"))
    )
    (net (code "50") (name "PWMD") (class "Default")
      (node (ref "U3") (pin "2") (pinfunction "IN_2") (pintype "passive"))
    )
    (net (code "51") (name "SO1") (class "Default")
      (node (ref "C25") (pin "1") (pinfunction "1_1") (pintype "passive"))
      (node (ref "R27") (pin "1") (pinfunction "1_1") (pintype "passive"))
    )
    (net (code "52") (name "SO2") (class "Default")
      (node (ref "C26") (pin "1") (pinfunction "1_1") (pintype "passive"))
      (node (ref "R30") (pin "1") (pinfunction "1_1") (pintype "passive"))
    )
    (net (code "53") (name "unconnected-(U-EN-Pad2)") (class "Default")
      (node (ref "U") (pin "2") (pinfunction "EN_2") (pintype "input"))
    )
  )
)
